# Practicum_MC_protoboard.net
KiCad netlist of a schematic drawn in EAGLE
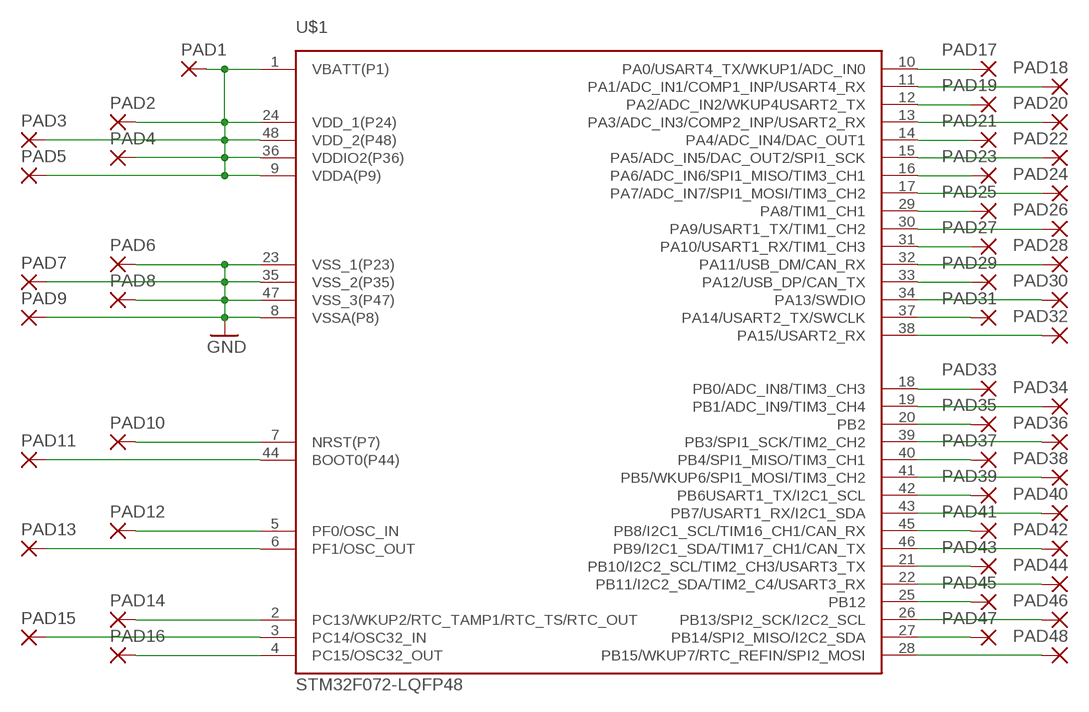
[diagram p0: schematic, sheet 1]

(export (version "E")
  (design (tool "Eeschema 10.0.6"))
  (components
    (comp (ref "PAD1")
      (value "SMD5")
      (footprint "eagle-import:SMD2,54-5,08")
      (libsource (lib "eagle-import") (part "SMD5"))
    )
    (comp (ref "PAD2")
      (value "SMD5")
      (footprint "eagle-import:SMD2,54-5,08")
      (libsource (lib "eagle-import") (part "SMD5"))
    )
    (comp (ref "PAD3")
      (value "SMD5")
      (footprint "eagle-import:SMD2,54-5,08")
      (libsource (lib "eagle-import") (part "SMD5"))
    )
    (comp (ref "PAD4")
      (value "SMD5")
      (footprint "eagle-import:SMD2,54-5,08")
      (libsource (lib "eagle-import") (part "SMD5"))
    )
    (comp (ref "PAD5")
      (value "SMD5")
      (footprint "eagle-import:SMD2,54-5,08")
      (libsource (lib "eagle-import") (part "SMD5"))
    )
    (comp (ref "PAD6")
      (value "SMD5")
      (footprint "eagle-import:SMD2,54-5,08")
      (libsource (lib "eagle-import") (part "SMD5"))
    )
    (comp (ref "PAD7")
      (value "SMD5")
      (footprint "eagle-import:SMD2,54-5,08")
      (libsource (lib "eagle-import") (part "SMD5"))
    )
    (comp (ref "PAD8")
      (value "SMD5")
      (footprint "eagle-import:SMD2,54-5,08")
      (libsource (lib "eagle-import") (part "SMD5"))
    )
    (comp (ref "PAD9")
      (value "SMD5")
      (footprint "eagle-import:SMD2,54-5,08")
      (libsource (lib "eagle-import") (part "SMD5"))
    )
    (comp (ref "PAD10")
      (value "SMD5")
      (footprint "eagle-import:SMD2,54-5,08")
      (libsource (lib "eagle-import") (part "SMD5"))
    )
    (comp (ref "PAD11")
      (value "SMD5")
      (footprint "eagle-import:SMD2,54-5,08")
      (libsource (lib "eagle-import") (part "SMD5"))
    )
    (comp (ref "PAD12")
      (value "SMD5")
      (footprint "eagle-import:SMD2,54-5,08")
      (libsource (lib "eagle-import") (part "SMD5"))
    )
    (comp (ref "PAD13")
      (value "SMD5")
      (footprint "eagle-import:SMD2,54-5,08")
      (libsource (lib "eagle-import") (part "SMD5"))
    )
    (comp (ref "PAD14")
      (value "SMD5")
      (footprint "eagle-import:SMD2,54-5,08")
      (libsource (lib "eagle-import") (part "SMD5"))
    )
    (comp (ref "PAD15")
      (value "SMD5")
      (footprint "eagle-import:SMD2,54-5,08")
      (libsource (lib "eagle-import") (part "SMD5"))
    )
    (comp (ref "PAD16")
      (value "SMD5")
      (footprint "eagle-import:SMD2,54-5,08")
      (libsource (lib "eagle-import") (part "SMD5"))
    )
    (comp (ref "PAD17")
      (value "SMD5")
      (footprint "eagle-import:SMD2,54-5,08")
      (libsource (lib "eagle-import") (part "SMD5"))
    )
    (comp (ref "PAD18")
      (value "SMD5")
      (footprint "eagle-import:SMD2,54-5,08")
      (libsource (lib "eagle-import") (part "SMD5"))
    )
    (comp (ref "PAD19")
      (value "SMD5")
      (footprint "eagle-import:SMD2,54-5,08")
      (libsource (lib "eagle-import") (part "SMD5"))
    )
    (comp (ref "PAD20")
      (value "SMD5")
      (footprint "eagle-import:SMD2,54-5,08")
      (libsource (lib "eagle-import") (part "SMD5"))
    )
    (comp (ref "PAD21")
      (value "SMD5")
      (footprint "eagle-import:SMD2,54-5,08")
      (libsource (lib "eagle-import") (part "SMD5"))
    )
    (comp (ref "PAD22")
      (value "SMD5")
      (footprint "eagle-import:SMD2,54-5,08")
      (libsource (lib "eagle-import") (part "SMD5"))
    )
    (comp (ref "PAD23")
      (value "SMD5")
      (footprint "eagle-import:SMD2,54-5,08")
      (libsource (lib "eagle-import") (part "SMD5"))
    )
    (comp (ref "PAD24")
      (value "SMD5")
      (footprint "eagle-import:SMD2,54-5,08")
      (libsource (lib "eagle-import") (part "SMD5"))
    )
    (comp (ref "PAD25")
      (value "SMD5")
      (footprint "eagle-import:SMD2,54-5,08")
      (libsource (lib "eagle-import") (part "SMD5"))
    )
    (comp (ref "PAD26")
      (value "SMD5")
      (footprint "eagle-import:SMD2,54-5,08")
      (libsource (lib "eagle-import") (part "SMD5"))
    )
    (comp (ref "PAD27")
      (value "SMD5")
      (footprint "eagle-import:SMD2,54-5,08")
      (libsource (lib "eagle-import") (part "SMD5"))
    )
    (comp (ref "PAD28")
      (value "SMD5")
      (footprint "eagle-import:SMD2,54-5,08")
      (libsource (lib "eagle-import") (part "SMD5"))
    )
    (comp (ref "PAD29")
      (value "SMD5")
      (footprint "eagle-import:SMD2,54-5,08")
      (libsource (lib "eagle-import") (part "SMD5"))
    )
    (comp (ref "PAD30")
      (value "SMD5")
      (footprint "eagle-import:SMD2,54-5,08")
      (libsource (lib "eagle-import") (part "SMD5"))
    )
    (comp (ref "PAD31")
      (value "SMD5")
      (footprint "eagle-import:SMD2,54-5,08")
      (libsource (lib "eagle-import") (part "SMD5"))
    )
    (comp (ref "PAD32")
      (value "SMD5")
      (footprint "eagle-import:SMD2,54-5,08")
      (libsource (lib "eagle-import") (part "SMD5"))
    )
    (comp (ref "PAD33")
      (value "SMD5")
      (footprint "eagle-import:SMD2,54-5,08")
      (libsource (lib "eagle-import") (part "SMD5"))
    )
    (comp (ref "PAD34")
      (value "SMD5")
      (footprint "eagle-import:SMD2,54-5,08")
      (libsource (lib "eagle-import") (part "SMD5"))
    )
    (comp (ref "PAD35")
      (value "SMD5")
      (footprint "eagle-import:SMD2,54-5,08")
      (libsource (lib "eagle-import") (part "SMD5"))
    )
    (comp (ref "PAD36")
      (value "SMD5")
      (footprint "eagle-import:SMD2,54-5,08")
      (libsource (lib "eagle-import") (part "SMD5"))
    )
    (comp (ref "PAD37")
      (value "SMD5")
      (footprint "eagle-import:SMD2,54-5,08")
      (libsource (lib "eagle-import") (part "SMD5"))
    )
    (comp (ref "PAD38")
      (value "SMD5")
      (footprint "eagle-import:SMD2,54-5,08")
      (libsource (lib "eagle-import") (part "SMD5"))
    )
    (comp (ref "PAD39")
      (value "SMD5")
      (footprint "eagle-import:SMD2,54-5,08")
      (libsource (lib "eagle-import") (part "SMD5"))
    )
    (comp (ref "PAD40")
      (value "SMD5")
      (footprint "eagle-import:SMD2,54-5,08")
      (libsource (lib "eagle-import") (part "SMD5"))
    )
    (comp (ref "PAD41")
      (value "SMD5")
      (footprint "eagle-import:SMD2,54-5,08")
      (libsource (lib "eagle-import") (part "SMD5"))
    )
    (comp (ref "PAD42")
      (value "SMD5")
      (footprint "eagle-import:SMD2,54-5,08")
      (libsource (lib "eagle-import") (part "SMD5"))
    )
    (comp (ref "PAD43")
      (value "SMD5")
      (footprint "eagle-import:SMD2,54-5,08")
      (libsource (lib "eagle-import") (part "SMD5"))
    )
    (comp (ref "PAD44")
      (value "SMD5")
      (footprint "eagle-import:SMD2,54-5,08")
      (libsource (lib "eagle-import") (part "SMD5"))
    )
    (comp (ref "PAD45")
      (value "SMD5")
      (footprint "eagle-import:SMD2,54-5,08")
      (libsource (lib "eagle-import") (part "SMD5"))
    )
    (comp (ref "PAD46")
      (value "SMD5")
      (footprint "eagle-import:SMD2,54-5,08")
      (libsource (lib "eagle-import") (part "SMD5"))
    )
    (comp (ref "PAD47")
      (value "SMD5")
      (footprint "eagle-import:SMD2,54-5,08")
      (libsource (lib "eagle-import") (part "SMD5"))
    )
    (comp (ref "PAD48")
      (value "SMD5")
      (footprint "eagle-import:SMD2,54-5,08")
      (libsource (lib "eagle-import") (part "SMD5"))
    )
    (comp (ref "U$1")
      (value "STM32F072-LQFP48")
      (footprint "eagle-import:LQFP48")
      (libsource (lib "eagle-import") (part "STM32F072-LQFP48"))
    )
  )
  (nets
    (net (code "1") (name "GND") (class "Default")
      (node (ref "PAD6") (pin "1") (pinfunction "P_1") (pintype "passive"))
      (node (ref "PAD7") (pin "1") (pinfunction "P_1") (pintype "passive"))
      (node (ref "PAD8") (pin "1") (pinfunction "P_1") (pintype "passive"))
      (node (ref "PAD9") (pin "1") (pinfunction "P_1") (pintype "passive"))
      (node (ref "U$1") (pin "23") (pinfunction "VSS_1(P23)_23") (pintype "bidirectional"))
      (node (ref "U$1") (pin "35") (pinfunction "VSS_2(P35)_35") (pintype "bidirectional"))
      (node (ref "U$1") (pin "47") (pinfunction "VSS_3(P47)_47") (pintype "bidirectional"))
      (node (ref "U$1") (pin "8") (pinfunction "VSSA(P8)_8") (pintype "bidirectional"))
    )
    (net (code "2") (name "Net-(PAD1-P)") (class "Default")
      (node (ref "PAD1") (pin "1") (pinfunction "P_1") (pintype "passive"))
      (node (ref "PAD2") (pin "1") (pinfunction "P_1") (pintype "passive"))
      (node (ref "PAD3") (pin "1") (pinfunction "P_1") (pintype "passive"))
      (node (ref "PAD4") (pin "1") (pinfunction "P_1") (pintype "passive"))
      (node (ref "PAD5") (pin "1") (pinfunction "P_1") (pintype "passive"))
      (node (ref "U$1") (pin "1") (pinfunction "VBATT(P1)_1") (pintype "bidirectional"))
      (node (ref "U$1") (pin "24") (pinfunction "VDD_1(P24)_24") (pintype "bidirectional"))
      (node (ref "U$1") (pin "36") (pinfunction "VDDIO2(P36)_36") (pintype "bidirectional"))
      (node (ref "U$1") (pin "48") (pinfunction "VDD_2(P48)_48") (pintype "bidirectional"))
      (node (ref "U$1") (pin "9") (pinfunction "VDDA(P9)_9") (pintype "bidirectional"))
    )
    (net (code "3") (name "Net-(PAD10-P)") (class "Default")
      (node (ref "PAD10") (pin "1") (pinfunction "P_1") (pintype "passive"))
      (node (ref "U$1") (pin "7") (pinfunction "NRST(P7)_7") (pintype "bidirectional"))
    )
    (net (code "4") (name "Net-(PAD11-P)") (class "Default")
      (node (ref "PAD11") (pin "1") (pinfunction "P_1") (pintype "passive"))
      (node (ref "U$1") (pin "44") (pinfunction "BOOT0(P44)_44") (pintype "bidirectional"))
    )
    (net (code "5") (name "Net-(PAD12-P)") (class "Default")
      (node (ref "PAD12") (pin "1") (pinfunction "P_1") (pintype "passive"))
      (node (ref "U$1") (pin "5") (pinfunction "PF0/OSC_IN_5") (pintype "bidirectional"))
    )
    (net (code "6") (name "Net-(PAD13-P)") (class "Default")
      (node (ref "PAD13") (pin "1") (pinfunction "P_1") (pintype "passive"))
      (node (ref "U$1") (pin "6") (pinfunction "PF1/OSC_OUT_6") (pintype "bidirectional"))
    )
    (net (code "7") (name "Net-(PAD14-P)") (class "Default")
      (node (ref "PAD14") (pin "1") (pinfunction "P_1") (pintype "passive"))
      (node (ref "U$1") (pin "2") (pinfunction "PC13/WKUP2/RTC_TAMP1/RTC_TS/RTC_OUT_2") (pintype "bidirectional"))
    )
    (net (code "8") (name "Net-(PAD15-P)") (class "Default")
      (node (ref "PAD15") (pin "1") (pinfunction "P_1") (pintype "passive"))
      (node (ref "U$1") (pin "3") (pinfunction "PC14/OSC32_IN_3") (pintype "bidirectional"))
    )
    (net (code "9") (name "Net-(PAD16-P)") (class "Default")
      (node (ref "PAD16") (pin "1") (pinfunction "P_1") (pintype "passive"))
      (node (ref "U$1") (pin "4") (pinfunction "PC15/OSC32_OUT_4") (pintype "bidirectional"))
    )
    (net (code "10") (name "Net-(PAD17-P)") (class "Default")
      (node (ref "PAD17") (pin "1") (pinfunction "P_1") (pintype "passive"))
      (node (ref "U$1") (pin "10") (pinfunction "PA0/USART4_TX/WKUP1/ADC_IN0_10") (pintype "bidirectional"))
    )
    (net (code "11") (name "Net-(PAD18-P)") (class "Default")
      (node (ref "PAD18") (pin "1") (pinfunction "P_1") (pintype "passive"))
      (node (ref "U$1") (pin "11") (pinfunction "PA1/ADC_IN1/COMP1_INP/USART4_RX_11") (pintype "bidirectional"))
    )
    (net (code "12") (name "Net-(PAD19-P)") (class "Default")
      (node (ref "PAD19") (pin "1") (pinfunction "P_1") (pintype "passive"))
      (node (ref "U$1") (pin "12") (pinfunction "PA2/ADC_IN2/WKUP4USART2_TX_12") (pintype "bidirectional"))
    )
    (net (code "13") (name "Net-(PAD20-P)") (class "Default")
      (node (ref "PAD20") (pin "1") (pinfunction "P_1") (pintype "passive"))
      (node (ref "U$1") (pin "13") (pinfunction "PA3/ADC_IN3/COMP2_INP/USART2_RX_13") (pintype "bidirectional"))
    )
    (net (code "14") (name "Net-(PAD21-P)") (class "Default")
      (node (ref "PAD21") (pin "1") (pinfunction "P_1") (pintype "passive"))
      (node (ref "U$1") (pin "14") (pinfunction "PA4/ADC_IN4/DAC_OUT1_14") (pintype "bidirectional"))
    )
    (net (code "15") (name "Net-(PAD22-P)") (class "Default")
      (node (ref "PAD22") (pin "1") (pinfunction "P_1") (pintype "passive"))
      (node (ref "U$1") (pin "15") (pinfunction "PA5/ADC_IN5/DAC_OUT2/SPI1_SCK_15") (pintype "bidirectional"))
    )
    (net (code "16") (name "Net-(PAD23-P)") (class "Default")
      (node (ref "PAD23") (pin "1") (pinfunction "P_1") (pintype "passive"))
      (node (ref "U$1") (pin "16") (pinfunction "PA6/ADC_IN6/SPI1_MISO/TIM3_CH1_16") (pintype "bidirectional"))
    )
    (net (code "17") (name "Net-(PAD24-P)") (class "Default")
      (node (ref "PAD24") (pin "1") (pinfunction "P_1") (pintype "passive"))
      (node (ref "U$1") (pin "17") (pinfunction "PA7/ADC_IN7/SPI1_MOSI/TIM3_CH2_17") (pintype "bidirectional"))
    )
    (net (code "18") (name "Net-(PAD25-P)") (class "Default")
      (node (ref "PAD25") (pin "1") (pinfunction "P_1") (pintype "passive"))
      (node (ref "U$1") (pin "29") (pinfunction "PA8/TIM1_CH1_29") (pintype "bidirectional"))
    )
    (net (code "19") (name "Net-(PAD26-P)") (class "Default")
      (node (ref "PAD26") (pin "1") (pinfunction "P_1") (pintype "passive"))
      (node (ref "U$1") (pin "30") (pinfunction "PA9/USART1_TX/TIM1_CH2_30") (pintype "bidirectional"))
    )
    (net (code "20") (name "Net-(PAD27-P)") (class "Default")
      (node (ref "PAD27") (pin "1") (pinfunction "P_1") (pintype "passive"))
      (node (ref "U$1") (pin "31") (pinfunction "PA10/USART1_RX/TIM1_CH3_31") (pintype "bidirectional"))
    )
    (net (code "21") (name "Net-(PAD28-P)") (class "Default")
      (node (ref "PAD28") (pin "1") (pinfunction "P_1") (pintype "passive"))
      (node (ref "U$1") (pin "32") (pinfunction "PA11/USB_DM/CAN_RX_32") (pintype "bidirectional"))
    )
    (net (code "22") (name "Net-(PAD29-P)") (class "Default")
      (node (ref "PAD29") (pin "1") (pinfunction "P_1") (pintype "passive"))
      (node (ref "U$1") (pin "33") (pinfunction "PA12/USB_DP/CAN_TX_33") (pintype "bidirectional"))
    )
    (net (code "23") (name "Net-(PAD30-P)") (class "Default")
      (node (ref "PAD30") (pin "1") (pinfunction "P_1") (pintype "passive"))
      (node (ref "U$1") (pin "34") (pinfunction "PA13/SWDIO_34") (pintype "bidirectional"))
    )
    (net (code "24") (name "Net-(PAD31-P)") (class "Default")
      (node (ref "PAD31") (pin "1") (pinfunction "P_1") (pintype "passive"))
      (node (ref "U$1") (pin "37") (pinfunction "PA14/USART2_TX/SWCLK_37") (pintype "bidirectional"))
    )
    (net (code "25") (name "Net-(PAD32-P)") (class "Default")
      (node (ref "PAD32") (pin "1") (pinfunction "P_1") (pintype "passive"))
      (node (ref "U$1") (pin "38") (pinfunction "PA15/USART2_RX_38") (pintype "bidirectional"))
    )
    (net (code "26") (name "Net-(PAD33-P)") (class "Default")
      (node (ref "PAD33") (pin "1") (pinfunction "P_1") (pintype "passive"))
      (node (ref "U$1") (pin "18") (pinfunction "PB0/ADC_IN8/TIM3_CH3_18") (pintype "bidirectional"))
    )
    (net (code "27") (name "Net-(PAD34-P)") (class "Default")
      (node (ref "PAD34") (pin "1") (pinfunction "P_1") (pintype "passive"))
      (node (ref "U$1") (pin "19") (pinfunction "PB1/ADC_IN9/TIM3_CH4_19") (pintype "bidirectional"))
    )
    (net (code "28") (name "Net-(PAD35-P)") (class "Default")
      (node (ref "PAD35") (pin "1") (pinfunction "P_1") (pintype "passive"))
      (node (ref "U$1") (pin "20") (pinfunction "PB2_20") (pintype "bidirectional"))
    )
    (net (code "29") (name "Net-(PAD36-P)") (class "Default")
      (node (ref "PAD36") (pin "1") (pinfunction "P_1") (pintype "passive"))
      (node (ref "U$1") (pin "39") (pinfunction "PB3/SPI1_SCK/TIM2_CH2_39") (pintype "bidirectional"))
    )
    (net (code "30") (name "Net-(PAD37-P)") (class "Default")
      (node (ref "PAD37") (pin "1") (pinfunction "P_1") (pintype "passive"))
      (node (ref "U$1") (pin "40") (pinfunction "PB4/SPI1_MISO/TIM3_CH1_40") (pintype "bidirectional"))
    )
    (net (code "31") (name "Net-(PAD38-P)") (class "Default")
      (node (ref "PAD38") (pin "1") (pinfunction "P_1") (pintype "passive"))
      (node (ref "U$1") (pin "41") (pinfunction "PB5/WKUP6/SPI1_MOSI/TIM3_CH2_41") (pintype "bidirectional"))
    )
    (net (code "32") (name "Net-(PAD39-P)") (class "Default")
      (node (ref "PAD39") (pin "1") (pinfunction "P_1") (pintype "passive"))
      (node (ref "U$1") (pin "42") (pinfunction "PB6USART1_TX/I2C1_SCL_42") (pintype "bidirectional"))
    )
    (net (code "33") (name "Net-(PAD40-P)") (class "Default")
      (node (ref "PAD40") (pin "1") (pinfunction "P_1") (pintype "passive"))
      (node (ref "U$1") (pin "43") (pinfunction "PB7/USART1_RX/I2C1_SDA_43") (pintype "bidirectional"))
    )
    (net (code "34") (name "Net-(PAD41-P)") (class "Default")
      (node (ref "PAD41") (pin "1") (pinfunction "P_1") (pintype "passive"))
      (node (ref "U$1") (pin "45") (pinfunction "PB8/I2C1_SCL/TIM16_CH1/CAN_RX_45") (pintype "bidirectional"))
    )
    (net (code "35") (name "Net-(PAD42-P)") (class "Default")
      (node (ref "PAD42") (pin "1") (pinfunction "P_1") (pintype "passive"))
      (node (ref "U$1") (pin "46") (pinfunction "PB9/I2C1_SDA/TIM17_CH1/CAN_TX_46") (pintype "bidirectional"))
    )
    (net (code "36") (name "Net-(PAD43-P)") (class "Default")
      (node (ref "PAD43") (pin "1") (pinfunction "P_1") (pintype "passive"))
      (node (ref "U$1") (pin "21") (pinfunction "PB10/I2C2_SCL/TIM2_CH3/USART3_TX_21") (pintype "bidirectional"))
    )
    (net (code "37") (name "Net-(PAD44-P)") (class "Default")
      (node (ref "PAD44") (pin "1") (pinfunction "P_1") (pintype "passive"))
      (node (ref "U$1") (pin "22") (pinfunction "PB11/I2C2_SDA/TIM2_C4/USART3_RX_22") (pintype "bidirectional"))
    )
    (net (code "38") (name "Net-(PAD45-P)") (class "Default")
      (node (ref "PAD45") (pin "1") (pinfunction "P_1") (pintype "passive"))
      (node (ref "U$1") (pin "25") (pinfunction "PB12_25") (pintype "bidirectional"))
    )
    (net (code "39") (name "Net-(PAD46-P)") (class "Default")
      (node (ref "PAD46") (pin "1") (pinfunction "P_1") (pintype "passive"))
      (node (ref "U$1") (pin "26") (pinfunction "PB13/SPI2_SCK/I2C2_SCL_26") (pintype "bidirectional"))
    )
    (net (code "40") (name "Net-(PAD47-P)") (class "Default")
      (node (ref "PAD47") (pin "1") (pinfunction "P_1") (pintype "passive"))
      (node (ref "U$1") (pin "27") (pinfunction "PB14/SPI2_MISO/I2C2_SDA_27") (pintype "bidirectional"))
    )
    (net (code "41") (name "Net-(PAD48-P)") (class "Default")
      (node (ref "PAD48") (pin "1") (pinfunction "P_1") (pintype "passive"))
      (node (ref "U$1") (pin "28") (pinfunction "PB15/WKUP7/RTC_REFIN/SPI2_MOSI_28") (pintype "bidirectional"))
    )
  )
)
